# Sequencer-V02-017.net
KiCad netlist of a schematic drawn in EAGLE
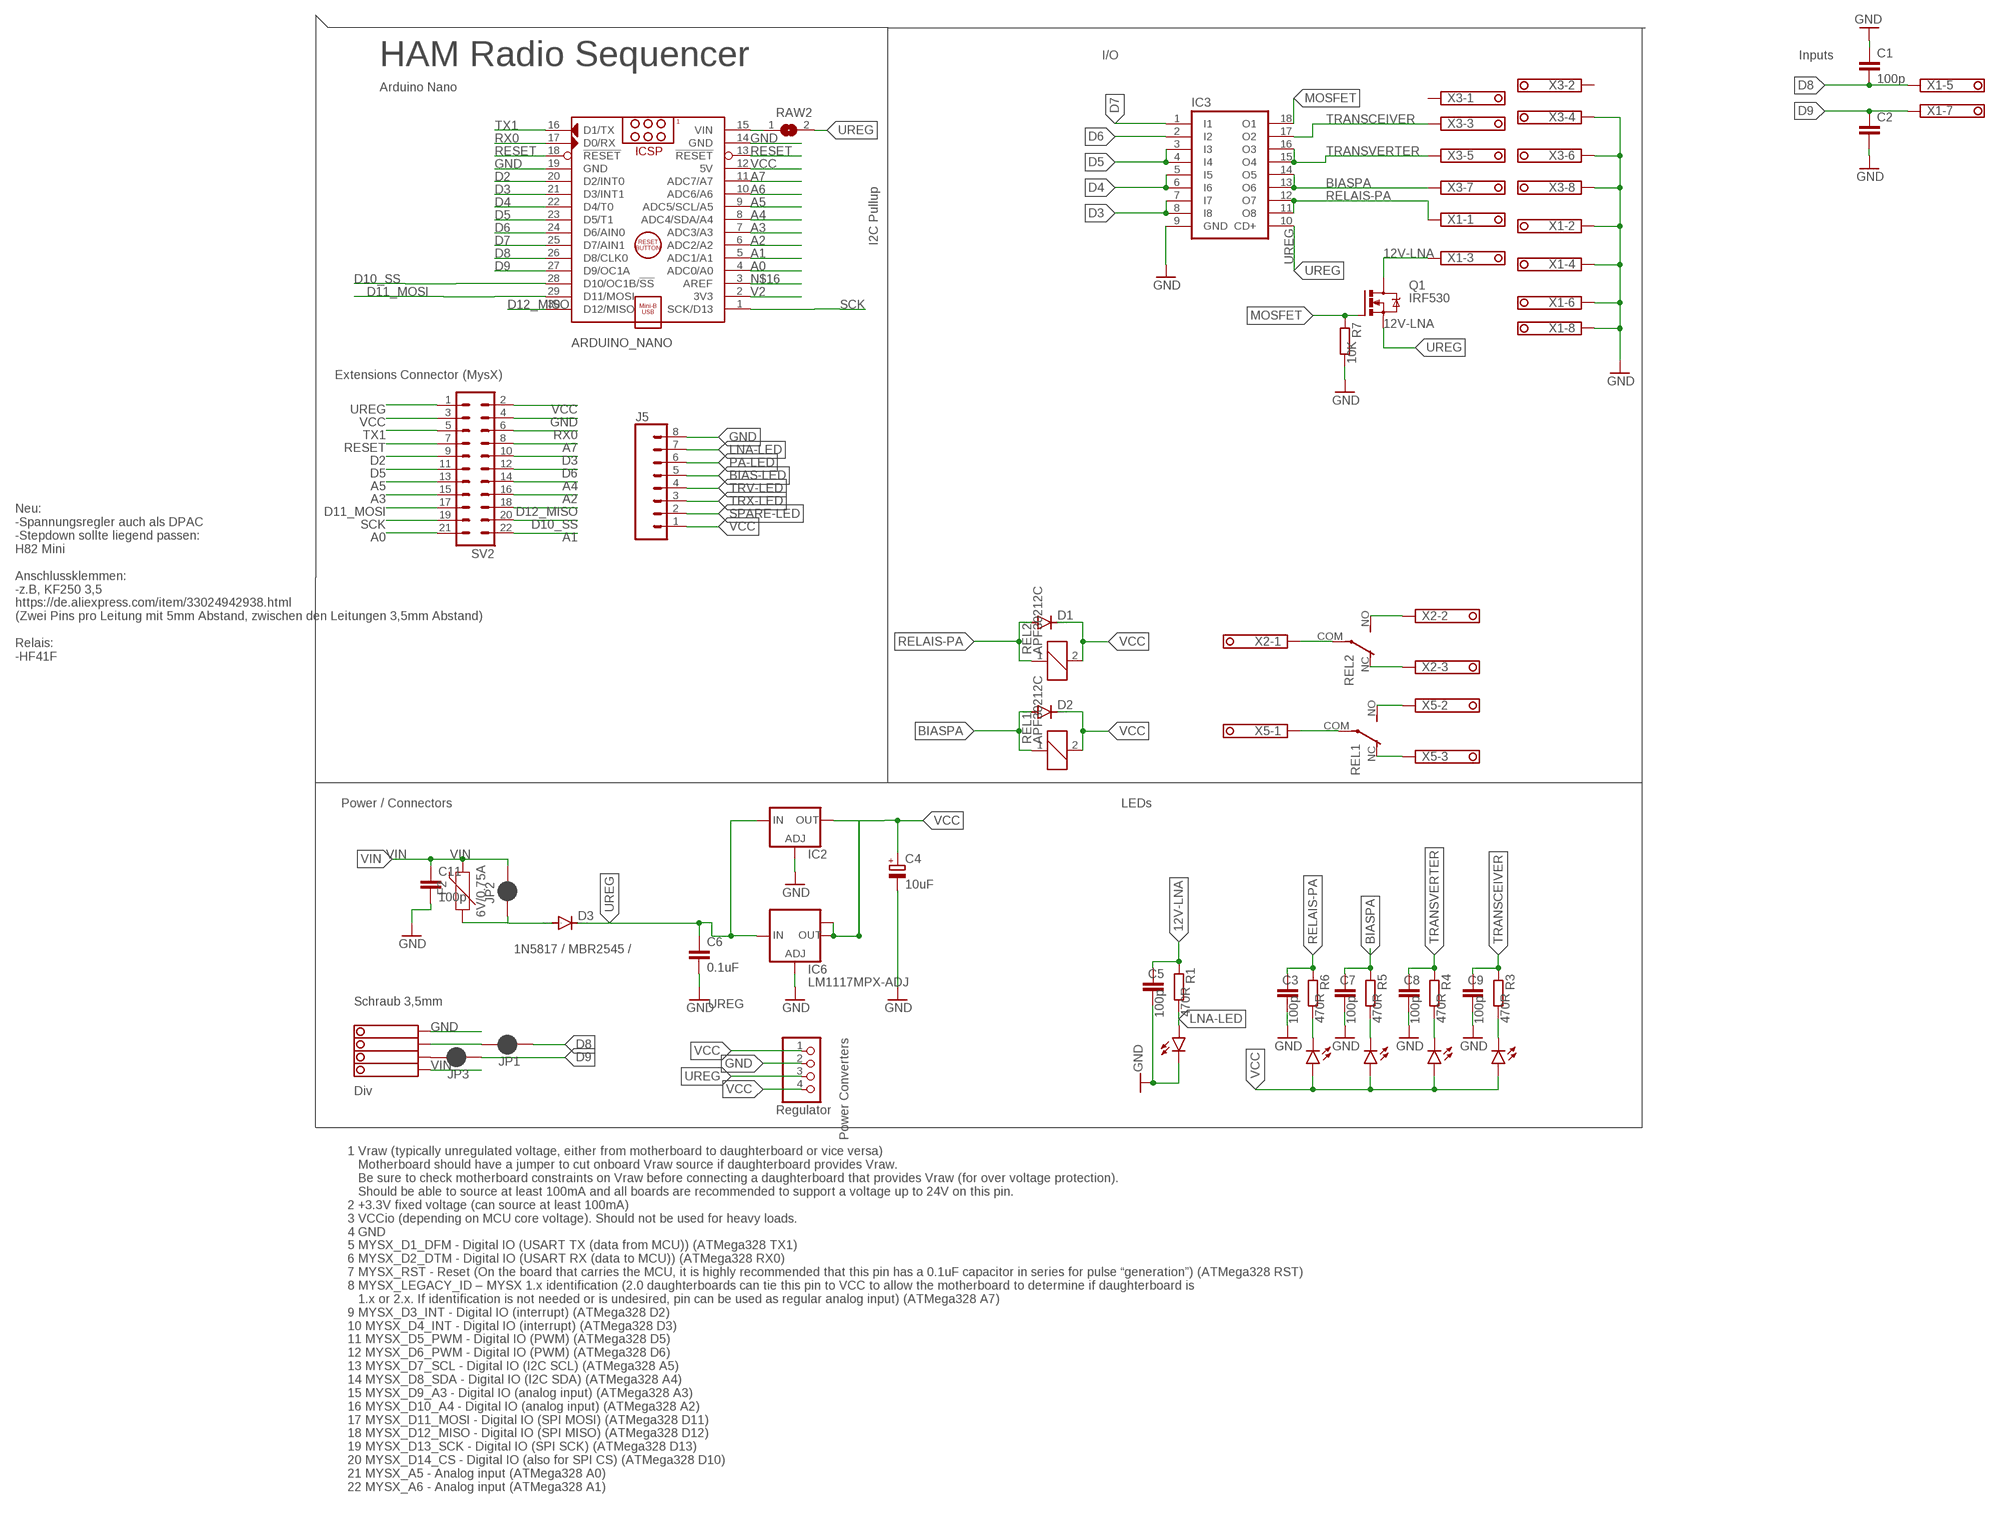
[diagram p0: schematic, sheet 1]

(export (version "E")
  (design (tool "Eeschema 10.0.6"))
  (components
    (comp (ref "ARDUINO_NANO")
      (value "ARDUINO_NANO_OHNE-BOHR")
      (footprint "eagle-import:ARDUINO_NANO")
      (libsource (lib "eagle-import") (part "ARDUINO_NANO_OHNE-BOHR"))
    )
    (comp (ref "C1")
      (value "100p")
      (footprint "eagle-import:C025-025X050")
      (libsource (lib "eagle-import") (part "C-EU025-025X050"))
    )
    (comp (ref "C2")
      (value "C-EU025-025X050")
      (footprint "eagle-import:C025-025X050")
      (libsource (lib "eagle-import") (part "C-EU025-025X050"))
    )
    (comp (ref "C3")
      (value "100p")
      (footprint "eagle-import:C025-025X050")
      (libsource (lib "eagle-import") (part "C-EU025-025X050"))
    )
    (comp (ref "C4")
      (value "10uF")
      (footprint "eagle-import:E3,5-8")
      (libsource (lib "eagle-import") (part "CPOL-EUE3.5-8"))
    )
    (comp (ref "C5")
      (value "100p")
      (footprint "eagle-import:C025-025X050")
      (libsource (lib "eagle-import") (part "C-EU025-025X050"))
    )
    (comp (ref "C6")
      (value "0.1uF")
      (footprint "eagle-import:C050-024X044")
      (libsource (lib "eagle-import") (part "C-EU050-024X044"))
    )
    (comp (ref "C7")
      (value "100p")
      (footprint "eagle-import:C025-025X050")
      (libsource (lib "eagle-import") (part "C-EU025-025X050"))
    )
    (comp (ref "C8")
      (value "100p")
      (footprint "eagle-import:C025-025X050")
      (libsource (lib "eagle-import") (part "C-EU025-025X050"))
    )
    (comp (ref "C9")
      (value "100p")
      (footprint "eagle-import:C025-025X050")
      (libsource (lib "eagle-import") (part "C-EU025-025X050"))
    )
    (comp (ref "C11")
      (value "100p")
      (footprint "eagle-import:C025-025X050")
      (libsource (lib "eagle-import") (part "C-EU025-025X050"))
    )
    (comp (ref "D1")
      (value "DIODE-D-2.5")
      (footprint "eagle-import:D-2.5")
      (libsource (lib "eagle-import") (part "DIODE-D-2.5"))
    )
    (comp (ref "D2")
      (value "DIODE-D-2.5")
      (footprint "eagle-import:D-2.5")
      (libsource (lib "eagle-import") (part "DIODE-D-2.5"))
    )
    (comp (ref "D3")
      (value "1N5817 / MBR2545 /")
      (footprint "eagle-import:D-2.5")
      (libsource (lib "eagle-import") (part "DIODE-D-2.5"))
    )
    (comp (ref "F2")
      (value "6V/0.75A")
      (footprint "eagle-import:1206")
      (libsource (lib "eagle-import") (part "PPTC_THREE-QUARTER-AMP"))
    )
    (comp (ref "IC2")
      (value "LD117ADT50TR")
      (footprint "eagle-import:DPACK")
      (libsource (lib "eagle-import") (part "LD117A?DT50TR"))
    )
    (comp (ref "IC3")
      (value "ULN2803A")
      (footprint "eagle-import:DIL18")
      (libsource (lib "eagle-import") (part "ULN2803A"))
    )
    (comp (ref "IC6")
      (value "LM1117MPX-ADJ")
      (footprint "eagle-import:SOT223")
      (libsource (lib "eagle-import") (part "LM1117MPX-ADJ"))
    )
    (comp (ref "J5")
      (value "CONN_08LOCK")
      (footprint "eagle-import:1X08_LOCK")
      (libsource (lib "eagle-import") (part "CONN_08LOCK"))
    )
    (comp (ref "JP1")
      (value "JUMPER-SMT_2_NC_PASTE_NO-SILK")
      (footprint "eagle-import:SMT-JUMPER_2_NC_PASTE_NO-SILK")
      (libsource (lib "eagle-import") (part "JUMPER-SMT_2_NC_PASTE_NO-SILK"))
    )
    (comp (ref "JP2")
      (value "JUMPER-SMT_2_NC_PASTE_NO-SILK")
      (footprint "eagle-import:SMT-JUMPER_2_NC_PASTE_NO-SILK")
      (libsource (lib "eagle-import") (part "JUMPER-SMT_2_NC_PASTE_NO-SILK"))
    )
    (comp (ref "JP3")
      (value "JUMPER-SMT_2_NC_PASTE_NO-SILK")
      (footprint "eagle-import:SMT-JUMPER_2_NC_PASTE_NO-SILK")
      (libsource (lib "eagle-import") (part "JUMPER-SMT_2_NC_PASTE_NO-SILK"))
    )
    (comp (ref "LED1")
      (value "LED3MM")
      (footprint "eagle-import:LED3MM")
      (libsource (lib "eagle-import") (part "LED3MM"))
    )
    (comp (ref "LED3")
      (value "LED3MM")
      (footprint "eagle-import:LED3MM")
      (libsource (lib "eagle-import") (part "LED3MM"))
    )
    (comp (ref "LED4")
      (value "LED3MM")
      (footprint "eagle-import:LED3MM")
      (libsource (lib "eagle-import") (part "LED3MM"))
    )
    (comp (ref "LED5")
      (value "LED3MM")
      (footprint "eagle-import:LED3MM")
      (libsource (lib "eagle-import") (part "LED3MM"))
    )
    (comp (ref "LED6")
      (value "LED3MM")
      (footprint "eagle-import:LED3MM")
      (libsource (lib "eagle-import") (part "LED3MM"))
    )
    (comp (ref "Q1")
      (value "IRF530")
      (footprint "eagle-import:TO220BV")
      (libsource (lib "eagle-import") (part "IRF530"))
    )
    (comp (ref "R1")
      (value "470R")
      (footprint "eagle-import:0204_5")
      (libsource (lib "eagle-import") (part "R-EU_0204/5"))
    )
    (comp (ref "R3")
      (value "470R")
      (footprint "eagle-import:0204_5")
      (libsource (lib "eagle-import") (part "R-EU_0204/5"))
    )
    (comp (ref "R4")
      (value "470R")
      (footprint "eagle-import:0204_5")
      (libsource (lib "eagle-import") (part "R-EU_0204/5"))
    )
    (comp (ref "R5")
      (value "470R")
      (footprint "eagle-import:0204_5")
      (libsource (lib "eagle-import") (part "R-EU_0204/5"))
    )
    (comp (ref "R6")
      (value "470R")
      (footprint "eagle-import:0204_5")
      (libsource (lib "eagle-import") (part "R-EU_0204/5"))
    )
    (comp (ref "R7")
      (value "10K")
      (footprint "eagle-import:0204_5")
      (libsource (lib "eagle-import") (part "R-EU_0204/5"))
    )
    (comp (ref "RAW2")
      (value "SJ")
      (footprint "eagle-import:SJ")
      (libsource (lib "eagle-import") (part "SJ"))
    )
    (comp (ref "REL1")
      (value "APF30212C")
      (footprint "eagle-import:APF30212C")
      (libsource (lib "eagle-import") (part "APF30212C"))
    )
    (comp (ref "REL2")
      (value "APF30212C")
      (footprint "eagle-import:APF30212C")
      (libsource (lib "eagle-import") (part "APF30212C"))
    )
    (comp (ref "STEPDWN")
      (value "PINHD-1X04_2.54-S")
      (footprint "eagle-import:1X04-S")
      (libsource (lib "eagle-import") (part "PINHD-1X04_2.54-S"))
    )
    (comp (ref "SV2")
      (value "MA11-2")
      (footprint "eagle-import:MA11-2")
      (libsource (lib "eagle-import") (part "MA11-2"))
    )
    (comp (ref "X1")
      (value "MARTIN8X2-1751303")
      (footprint "eagle-import:1751303")
      (libsource (lib "eagle-import") (part "MARTIN8X2-1751303"))
    )
    (comp (ref "X2")
      (value "MARTIN3X2-1751303175L303-3")
      (footprint "eagle-import:1751303-3")
      (libsource (lib "eagle-import") (part "MARTIN3X2-1751303175L303-3"))
    )
    (comp (ref "X3")
      (value "MARTIN8X2-1751303")
      (footprint "eagle-import:1751303")
      (libsource (lib "eagle-import") (part "MARTIN8X2-1751303"))
    )
    (comp (ref "X4")
      (value "1751264")
      (footprint "eagle-import:1751264")
      (libsource (lib "eagle-import") (part "1751264"))
    )
    (comp (ref "X5")
      (value "MARTIN3X2-1751303175L303-3")
      (footprint "eagle-import:1751303-3")
      (libsource (lib "eagle-import") (part "MARTIN3X2-1751303175L303-3"))
    )
  )
  (nets
    (net (code "1") (name "/A0") (class "Default")
      (node (ref "ARDUINO_NANO") (pin "4") (pinfunction "ADC0/A0_4") (pintype "bidirectional"))
      (node (ref "SV2") (pin "21") (pinfunction "21_21") (pintype "passive"))
    )
    (net (code "2") (name "/A1") (class "Default")
      (node (ref "ARDUINO_NANO") (pin "5") (pinfunction "ADC1/A1_5") (pintype "bidirectional"))
      (node (ref "SV2") (pin "22") (pinfunction "22_22") (pintype "passive"))
    )
    (net (code "3") (name "/A2") (class "Default")
      (node (ref "ARDUINO_NANO") (pin "6") (pinfunction "ADC2/A2_6") (pintype "bidirectional"))
      (node (ref "SV2") (pin "16") (pinfunction "16_16") (pintype "passive"))
    )
    (net (code "4") (name "/A3") (class "Default")
      (node (ref "ARDUINO_NANO") (pin "7") (pinfunction "ADC3/A3_7") (pintype "bidirectional"))
      (node (ref "SV2") (pin "15") (pinfunction "15_15") (pintype "passive"))
    )
    (net (code "5") (name "/A4") (class "Default")
      (node (ref "ARDUINO_NANO") (pin "8") (pinfunction "ADC4/SDA/A4_8") (pintype "bidirectional"))
      (node (ref "SV2") (pin "14") (pinfunction "14_14") (pintype "passive"))
    )
    (net (code "6") (name "/A5") (class "Default")
      (node (ref "ARDUINO_NANO") (pin "9") (pinfunction "ADC5/SCL/A5_9") (pintype "bidirectional"))
      (node (ref "SV2") (pin "13") (pinfunction "13_13") (pintype "passive"))
    )
    (net (code "7") (name "/A6") (class "Default")
      (node (ref "ARDUINO_NANO") (pin "10") (pinfunction "ADC6/A6_10") (pintype "bidirectional"))
    )
    (net (code "8") (name "/A7") (class "Default")
      (node (ref "ARDUINO_NANO") (pin "11") (pinfunction "ADC7/A7_11") (pintype "bidirectional"))
      (node (ref "SV2") (pin "8") (pinfunction "8_8") (pintype "passive"))
    )
    (net (code "9") (name "/D2") (class "Default")
      (node (ref "ARDUINO_NANO") (pin "20") (pinfunction "D2/INT0_20") (pintype "bidirectional"))
      (node (ref "SV2") (pin "9") (pinfunction "9_9") (pintype "passive"))
    )
    (net (code "10") (name "/D10_SS") (class "Default")
      (node (ref "ARDUINO_NANO") (pin "28") (pinfunction "D10/OC1B/~{SS}_28") (pintype "bidirectional"))
      (node (ref "SV2") (pin "20") (pinfunction "20_20") (pintype "passive"))
    )
    (net (code "11") (name "/D11_MOSI") (class "Default")
      (node (ref "ARDUINO_NANO") (pin "29") (pinfunction "D11/MOSI_29") (pintype "bidirectional"))
      (node (ref "SV2") (pin "17") (pinfunction "17_17") (pintype "passive"))
    )
    (net (code "12") (name "/D12_MISO") (class "Default")
      (node (ref "ARDUINO_NANO") (pin "30") (pinfunction "D12/MISO_30") (pintype "bidirectional"))
      (node (ref "SV2") (pin "18") (pinfunction "18_18") (pintype "passive"))
    )
    (net (code "13") (name "/N$16") (class "Default")
      (node (ref "ARDUINO_NANO") (pin "3") (pinfunction "AREF_3") (pintype "input"))
    )
    (net (code "14") (name "/RESET") (class "Default")
      (node (ref "ARDUINO_NANO") (pin "13") (pinfunction "~{RESET}_13") (pintype "input"))
      (node (ref "ARDUINO_NANO") (pin "18") (pinfunction "~{RESET}_18") (pintype "input"))
      (node (ref "SV2") (pin "7") (pinfunction "7_7") (pintype "passive"))
    )
    (net (code "15") (name "/RX0") (class "Default")
      (node (ref "ARDUINO_NANO") (pin "17") (pinfunction "D0/RX_17") (pintype "bidirectional"))
      (node (ref "SV2") (pin "6") (pinfunction "6_6") (pintype "passive"))
    )
    (net (code "16") (name "/SCK") (class "Default")
      (node (ref "ARDUINO_NANO") (pin "1") (pinfunction "SCK/D13_1") (pintype "bidirectional"))
      (node (ref "SV2") (pin "19") (pinfunction "19_19") (pintype "passive"))
    )
    (net (code "17") (name "/TX1") (class "Default")
      (node (ref "ARDUINO_NANO") (pin "16") (pinfunction "D1/TX_16") (pintype "bidirectional"))
      (node (ref "SV2") (pin "5") (pinfunction "5_5") (pintype "passive"))
    )
    (net (code "18") (name "/V2") (class "Default")
      (node (ref "ARDUINO_NANO") (pin "2") (pinfunction "3V3_2") (pintype "output"))
    )
    (net (code "19") (name "12V-LNA") (class "Default")
      (node (ref "C5") (pin "1") (pinfunction "1_1") (pintype "passive"))
      (node (ref "Q1") (pin "D") (pinfunction "D_D") (pintype "passive"))
      (node (ref "R1") (pin "1") (pinfunction "1_1") (pintype "passive"))
      (node (ref "X1") (pin "11") (pinfunction "K_11") (pintype "passive"))
    )
    (net (code "20") (name "BIAS-LED") (class "Default")
      (node (ref "J5") (pin "5") (pinfunction "5_5") (pintype "passive"))
      (node (ref "LED5") (pin "K") (pinfunction "C_K") (pintype "passive"))
      (node (ref "R5") (pin "2") (pinfunction "2_2") (pintype "passive"))
    )
    (net (code "21") (name "BIASPA") (class "Default")
      (node (ref "C7") (pin "1") (pinfunction "1_1") (pintype "passive"))
      (node (ref "D2") (pin "A") (pinfunction "A_A") (pintype "passive"))
      (node (ref "IC3") (pin "13") (pinfunction "O6_13") (pintype "open_collector"))
      (node (ref "IC3") (pin "14") (pinfunction "O5_14") (pintype "open_collector"))
      (node (ref "R5") (pin "1") (pinfunction "1_1") (pintype "passive"))
      (node (ref "REL1") (pin "1") (pinfunction "1_1") (pintype "passive"))
      (node (ref "X3") (pin "15") (pinfunction "K_15") (pintype "passive"))
    )
    (net (code "22") (name "D3") (class "Default")
      (node (ref "ARDUINO_NANO") (pin "21") (pinfunction "D3/INT1_21") (pintype "bidirectional"))
      (node (ref "IC3") (pin "7") (pinfunction "I7_7") (pintype "input"))
      (node (ref "IC3") (pin "8") (pinfunction "I8_8") (pintype "input"))
      (node (ref "SV2") (pin "10") (pinfunction "10_10") (pintype "passive"))
    )
    (net (code "23") (name "D4") (class "Default")
      (node (ref "ARDUINO_NANO") (pin "22") (pinfunction "D4/T0_22") (pintype "bidirectional"))
      (node (ref "IC3") (pin "5") (pinfunction "I5_5") (pintype "input"))
      (node (ref "IC3") (pin "6") (pinfunction "I6_6") (pintype "input"))
    )
    (net (code "24") (name "D5") (class "Default")
      (node (ref "ARDUINO_NANO") (pin "23") (pinfunction "D5/T1_23") (pintype "bidirectional"))
      (node (ref "IC3") (pin "3") (pinfunction "I3_3") (pintype "input"))
      (node (ref "IC3") (pin "4") (pinfunction "I4_4") (pintype "input"))
      (node (ref "SV2") (pin "11") (pinfunction "11_11") (pintype "passive"))
    )
    (net (code "25") (name "D6") (class "Default")
      (node (ref "ARDUINO_NANO") (pin "24") (pinfunction "D6/AIN0_24") (pintype "bidirectional"))
      (node (ref "IC3") (pin "2") (pinfunction "I2_2") (pintype "input"))
      (node (ref "SV2") (pin "12") (pinfunction "12_12") (pintype "passive"))
    )
    (net (code "26") (name "D7") (class "Default")
      (node (ref "ARDUINO_NANO") (pin "25") (pinfunction "D7/AIN1_25") (pintype "bidirectional"))
      (node (ref "IC3") (pin "1") (pinfunction "I1_1") (pintype "input"))
    )
    (net (code "27") (name "D8") (class "Default")
      (node (ref "ARDUINO_NANO") (pin "26") (pinfunction "D8/CLK0_26") (pintype "bidirectional"))
      (node (ref "C1") (pin "2") (pinfunction "2_2") (pintype "passive"))
      (node (ref "JP1") (pin "1") (pinfunction "1_1") (pintype "passive"))
      (node (ref "X1") (pin "13") (pinfunction "K_13") (pintype "passive"))
    )
    (net (code "28") (name "D9") (class "Default")
      (node (ref "ARDUINO_NANO") (pin "27") (pinfunction "D9/OC1A_27") (pintype "bidirectional"))
      (node (ref "C2") (pin "1") (pinfunction "1_1") (pintype "passive"))
      (node (ref "JP3") (pin "1") (pinfunction "1_1") (pintype "passive"))
      (node (ref "X1") (pin "15") (pinfunction "K_15") (pintype "passive"))
    )
    (net (code "29") (name "GND") (class "Default")
      (node (ref "ARDUINO_NANO") (pin "14") (pinfunction "GND_14") (pintype "power_in"))
      (node (ref "ARDUINO_NANO") (pin "19") (pinfunction "GND_19") (pintype "power_in"))
      (node (ref "C1") (pin "1") (pinfunction "1_1") (pintype "passive"))
      (node (ref "C11") (pin "2") (pinfunction "2_2") (pintype "passive"))
      (node (ref "C2") (pin "2") (pinfunction "2_2") (pintype "passive"))
      (node (ref "C3") (pin "2") (pinfunction "2_2") (pintype "passive"))
      (node (ref "C4") (pin "-") (pinfunction "-_-") (pintype "passive"))
      (node (ref "C5") (pin "2") (pinfunction "2_2") (pintype "passive"))
      (node (ref "C6") (pin "2") (pinfunction "2_2") (pintype "passive"))
      (node (ref "C7") (pin "2") (pinfunction "2_2") (pintype "passive"))
      (node (ref "C8") (pin "2") (pinfunction "2_2") (pintype "passive"))
      (node (ref "C9") (pin "2") (pinfunction "2_2") (pintype "passive"))
      (node (ref "IC2") (pin "1") (pinfunction "ADJ_1") (pintype "input"))
      (node (ref "IC3") (pin "9") (pinfunction "GND_9") (pintype "power_in"))
      (node (ref "IC6") (pin "1") (pinfunction "ADJ_1") (pintype "input"))
      (node (ref "J5") (pin "8") (pinfunction "8_8") (pintype "passive"))
      (node (ref "LED1") (pin "K") (pinfunction "C_K") (pintype "passive"))
      (node (ref "R7") (pin "2") (pinfunction "2_2") (pintype "passive"))
      (node (ref "STEPDWN") (pin "2") (pinfunction "2_2") (pintype "passive"))
      (node (ref "SV2") (pin "4") (pinfunction "4_4") (pintype "passive"))
      (node (ref "X1") (pin "10") (pinfunction "K_10") (pintype "passive"))
      (node (ref "X1") (pin "12") (pinfunction "K_12") (pintype "passive"))
      (node (ref "X1") (pin "14") (pinfunction "K_14") (pintype "passive"))
      (node (ref "X1") (pin "16") (pinfunction "K_16") (pintype "passive"))
      (node (ref "X3") (pin "12") (pinfunction "K_12") (pintype "passive"))
      (node (ref "X3") (pin "14") (pinfunction "K_14") (pintype "passive"))
      (node (ref "X3") (pin "16") (pinfunction "K_16") (pintype "passive"))
      (node (ref "X4") (pin "4") (pinfunction "K_4") (pintype "passive"))
    )
    (net (code "30") (name "LNA-LED") (class "Default")
      (node (ref "J5") (pin "7") (pinfunction "7_7") (pintype "passive"))
      (node (ref "LED1") (pin "A") (pinfunction "A_A") (pintype "passive"))
      (node (ref "R1") (pin "2") (pinfunction "2_2") (pintype "passive"))
    )
    (net (code "31") (name "MOSFET") (class "Default")
      (node (ref "IC3") (pin "18") (pinfunction "O1_18") (pintype "open_collector"))
      (node (ref "Q1") (pin "G") (pinfunction "G_G") (pintype "passive"))
      (node (ref "R7") (pin "1") (pinfunction "1_1") (pintype "passive"))
    )
    (net (code "32") (name "Net-(ARDUINO_NANO-VIN)") (class "Default")
      (node (ref "ARDUINO_NANO") (pin "15") (pinfunction "VIN_15") (pintype "power_in"))
      (node (ref "RAW2") (pin "1") (pinfunction "1_1") (pintype "passive"))
    )
    (net (code "33") (name "Net-(D3-PadA)") (class "Default")
      (node (ref "D3") (pin "A") (pinfunction "A_A") (pintype "passive"))
      (node (ref "F2") (pin "1") (pinfunction "1_1") (pintype "bidirectional"))
      (node (ref "JP2") (pin "1") (pinfunction "1_1") (pintype "passive"))
    )
    (net (code "34") (name "Net-(REL1B-O)") (class "Default")
      (node (ref "REL1") (pin "NC") (pinfunction "O_NC") (pintype "passive"))
      (node (ref "X5") (pin "3") (pinfunction "K_3") (pintype "passive"))
    )
    (net (code "35") (name "Net-(REL1B-P)") (class "Default")
      (node (ref "REL1") (pin "COM") (pinfunction "P_COM") (pintype "passive"))
      (node (ref "X5") (pin "1") (pinfunction "K_1") (pintype "passive"))
    )
    (net (code "36") (name "Net-(REL1B-S)") (class "Default")
      (node (ref "REL1") (pin "NO") (pinfunction "S_NO") (pintype "passive"))
      (node (ref "X5") (pin "2") (pinfunction "K_2") (pintype "passive"))
    )
    (net (code "37") (name "Net-(REL2B-O)") (class "Default")
      (node (ref "REL2") (pin "NC") (pinfunction "O_NC") (pintype "passive"))
      (node (ref "X2") (pin "3") (pinfunction "K_3") (pintype "passive"))
    )
    (net (code "38") (name "Net-(REL2B-P)") (class "Default")
      (node (ref "REL2") (pin "COM") (pinfunction "P_COM") (pintype "passive"))
      (node (ref "X2") (pin "1") (pinfunction "K_1") (pintype "passive"))
    )
    (net (code "39") (name "Net-(REL2B-S)") (class "Default")
      (node (ref "REL2") (pin "NO") (pinfunction "S_NO") (pintype "passive"))
      (node (ref "X2") (pin "2") (pinfunction "K_2") (pintype "passive"))
    )
    (net (code "40") (name "Net-(X4B-K)") (class "Default")
      (node (ref "JP3") (pin "2") (pinfunction "2_2") (pintype "passive"))
      (node (ref "X4") (pin "2") (pinfunction "K_2") (pintype "passive"))
    )
    (net (code "41") (name "Net-(X4C-K)") (class "Default")
      (node (ref "JP1") (pin "2") (pinfunction "2_2") (pintype "passive"))
      (node (ref "X4") (pin "3") (pinfunction "K_3") (pintype "passive"))
    )
    (net (code "42") (name "PA-LED") (class "Default")
      (node (ref "J5") (pin "6") (pinfunction "6_6") (pintype "passive"))
      (node (ref "LED6") (pin "K") (pinfunction "C_K") (pintype "passive"))
      (node (ref "R6") (pin "2") (pinfunction "2_2") (pintype "passive"))
    )
    (net (code "43") (name "RELAIS-PA") (class "Default")
      (node (ref "C3") (pin "1") (pinfunction "1_1") (pintype "passive"))
      (node (ref "D1") (pin "A") (pinfunction "A_A") (pintype "passive"))
      (node (ref "IC3") (pin "11") (pinfunction "O8_11") (pintype "open_collector"))
      (node (ref "IC3") (pin "12") (pinfunction "O7_12") (pintype "open_collector"))
      (node (ref "R6") (pin "1") (pinfunction "1_1") (pintype "passive"))
      (node (ref "REL2") (pin "1") (pinfunction "1_1") (pintype "passive"))
      (node (ref "X1") (pin "9") (pinfunction "K_9") (pintype "passive"))
    )
    (net (code "44") (name "SPARE-LED") (class "Default")
      (node (ref "J5") (pin "2") (pinfunction "2_2") (pintype "passive"))
    )
    (net (code "45") (name "TRANSCEIVER") (class "Default")
      (node (ref "C9") (pin "1") (pinfunction "1_1") (pintype "passive"))
      (node (ref "IC3") (pin "17") (pinfunction "O2_17") (pintype "open_collector"))
      (node (ref "R3") (pin "1") (pinfunction "1_1") (pintype "passive"))
      (node (ref "X3") (pin "11") (pinfunction "K_11") (pintype "passive"))
    )
    (net (code "46") (name "TRANSVERTER") (class "Default")
      (node (ref "C8") (pin "1") (pinfunction "1_1") (pintype "passive"))
      (node (ref "IC3") (pin "15") (pinfunction "O4_15") (pintype "open_collector"))
      (node (ref "IC3") (pin "16") (pinfunction "O3_16") (pintype "open_collector"))
      (node (ref "R4") (pin "1") (pinfunction "1_1") (pintype "passive"))
      (node (ref "X3") (pin "13") (pinfunction "K_13") (pintype "passive"))
    )
    (net (code "47") (name "TRV-LED") (class "Default")
      (node (ref "J5") (pin "4") (pinfunction "4_4") (pintype "passive"))
      (node (ref "LED4") (pin "K") (pinfunction "C_K") (pintype "passive"))
      (node (ref "R4") (pin "2") (pinfunction "2_2") (pintype "passive"))
    )
    (net (code "48") (name "TRX-LED") (class "Default")
      (node (ref "J5") (pin "3") (pinfunction "3_3") (pintype "passive"))
      (node (ref "LED3") (pin "K") (pinfunction "C_K") (pintype "passive"))
      (node (ref "R3") (pin "2") (pinfunction "2_2") (pintype "passive"))
    )
    (net (code "49") (name "UREG") (class "Default")
      (node (ref "C6") (pin "1") (pinfunction "1_1") (pintype "passive"))
      (node (ref "D3") (pin "C") (pinfunction "C_C") (pintype "passive"))
      (node (ref "IC2") (pin "3") (pinfunction "IN_3") (pintype "input"))
      (node (ref "IC3") (pin "10") (pinfunction "CD+_10") (pintype "passive"))
      (node (ref "IC6") (pin "3") (pinfunction "IN_3") (pintype "input"))
      (node (ref "Q1") (pin "S") (pinfunction "S_S") (pintype "passive"))
      (node (ref "RAW2") (pin "2") (pinfunction "2_2") (pintype "passive"))
      (node (ref "STEPDWN") (pin "3") (pinfunction "3_3") (pintype "passive"))
      (node (ref "SV2") (pin "1") (pinfunction "1_1") (pintype "passive"))
    )
    (net (code "50") (name "VCC") (class "Default")
      (node (ref "ARDUINO_NANO") (pin "12") (pinfunction "5V_12") (pintype "power_in"))
      (node (ref "C4") (pin "+") (pinfunction "+_+") (pintype "passive"))
      (node (ref "D1") (pin "C") (pinfunction "C_C") (pintype "passive"))
      (node (ref "D2") (pin "C") (pinfunction "C_C") (pintype "passive"))
      (node (ref "IC2") (pin "4") (pinfunction "OUT_4") (pintype "passive"))
      (node (ref "IC6") (pin "2") (pinfunction "OUT_2") (pintype "passive"))
      (node (ref "IC6") (pin "TAB") (pinfunction "OUT1_TAB") (pintype "passive"))
      (node (ref "J5") (pin "1") (pinfunction "1_1") (pintype "passive"))
      (node (ref "LED3") (pin "A") (pinfunction "A_A") (pintype "passive"))
      (node (ref "LED4") (pin "A") (pinfunction "A_A") (pintype "passive"))
      (node (ref "LED5") (pin "A") (pinfunction "A_A") (pintype "passive"))
      (node (ref "LED6") (pin "A") (pinfunction "A_A") (pintype "passive"))
      (node (ref "REL1") (pin "2") (pinfunction "2_2") (pintype "passive"))
      (node (ref "REL2") (pin "2") (pinfunction "2_2") (pintype "passive"))
      (node (ref "STEPDWN") (pin "1") (pinfunction "1_1") (pintype "passive"))
      (node (ref "STEPDWN") (pin "4") (pinfunction "4_4") (pintype "passive"))
      (node (ref "SV2") (pin "2") (pinfunction "2_2") (pintype "passive"))
      (node (ref "SV2") (pin "3") (pinfunction "3_3") (pintype "passive"))
    )
    (net (code "51") (name "VIN") (class "Default")
      (node (ref "C11") (pin "1") (pinfunction "1_1") (pintype "passive"))
      (node (ref "F2") (pin "2") (pinfunction "2_2") (pintype "bidirectional"))
      (node (ref "JP2") (pin "2") (pinfunction "2_2") (pintype "passive"))
      (node (ref "X4") (pin "1") (pinfunction "K_1") (pintype "passive"))
    )
    (net (code "52") (name "unconnected-(X3A-K-Pad9)") (class "Default")
      (node (ref "X3") (pin "9") (pinfunction "K_9") (pintype "passive"))
    )
    (net (code "53") (name "unconnected-(X3B-K-Pad10)") (class "Default")
      (node (ref "X3") (pin "10") (pinfunction "K_10") (pintype "passive"))
    )
  )
)
